# ProPrj_USBuddy_2026-04-30.net
KiCad netlist of a schematic drawn in EasyEDA Pro
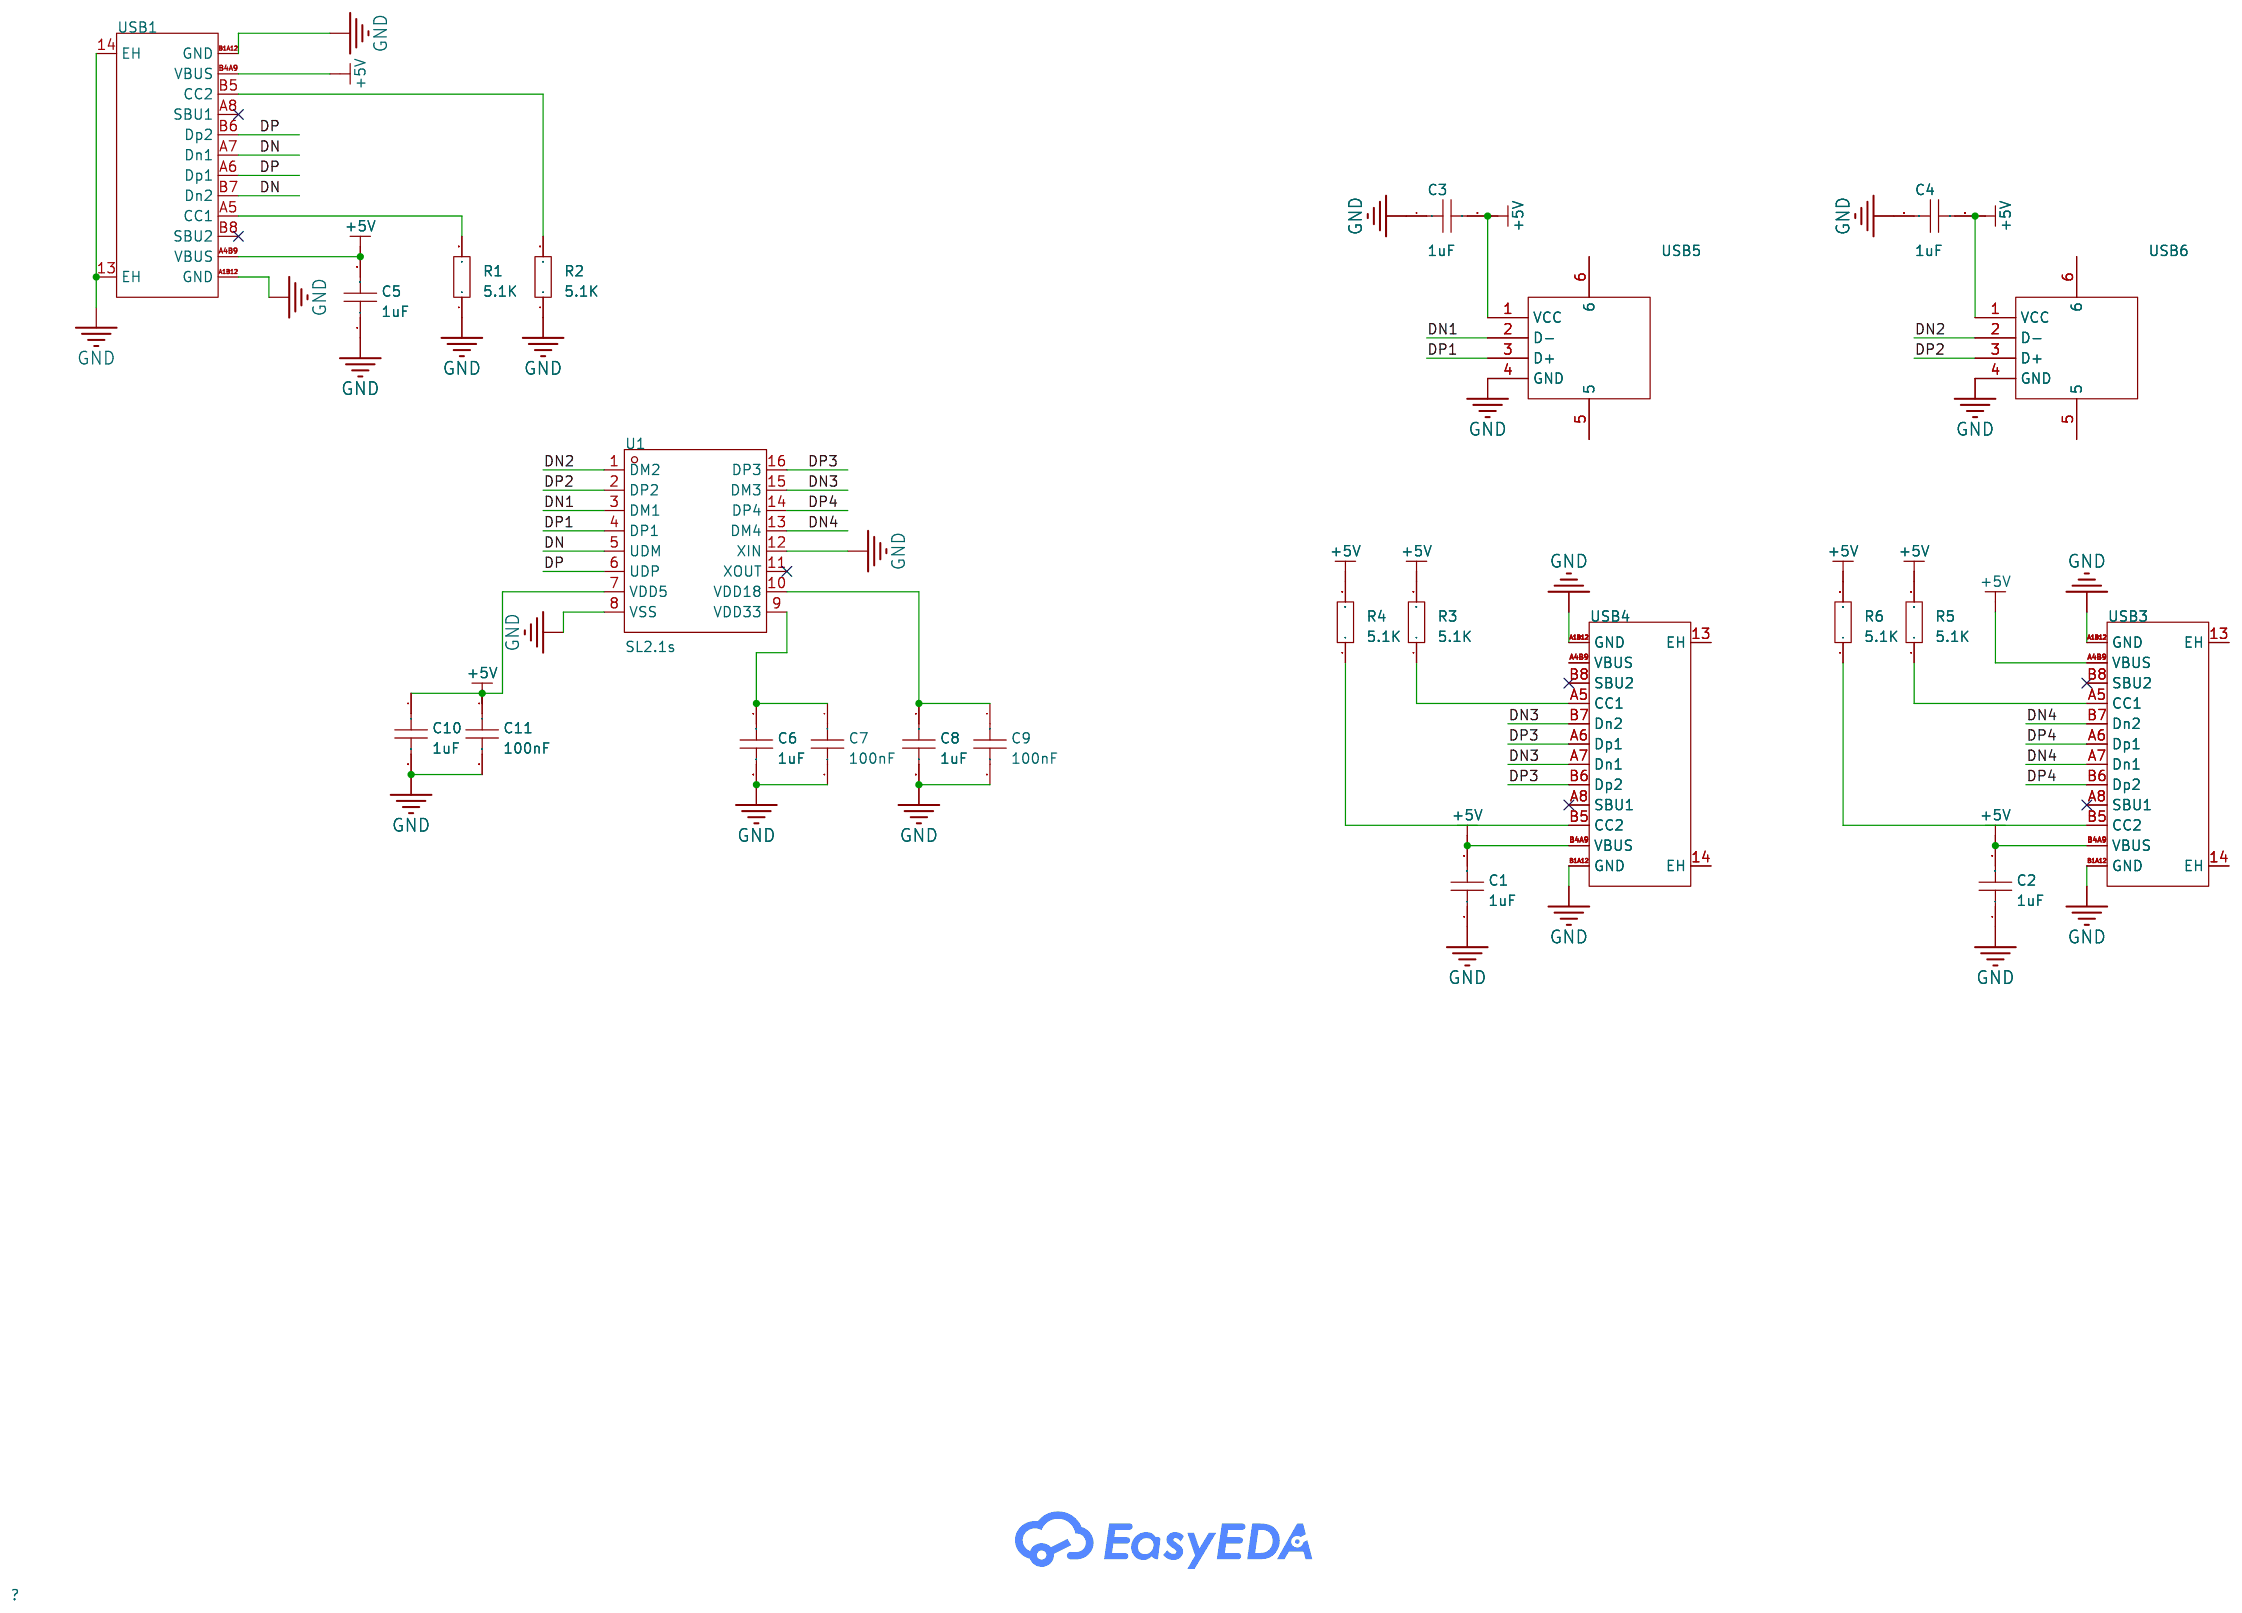
[diagram p0: schematic sheet]

(export (version "E")
  (design (tool "Eeschema 10.0.6"))
  (components
    (comp (ref "C1") (value "1uF") (footprint "easyedapro:C0603") (libsource (lib "easyedapro") (part "CAP")))
    (comp (ref "C2") (value "1uF") (footprint "easyedapro:C0603") (libsource (lib "easyedapro") (part "CAP")))
    (comp (ref "C3") (value "1uF") (footprint "easyedapro:C0603") (libsource (lib "easyedapro") (part "CAP")))
    (comp (ref "C4") (value "1uF") (footprint "easyedapro:C0603") (libsource (lib "easyedapro") (part "CAP")))
    (comp (ref "C5") (value "1uF") (footprint "easyedapro:C0603") (libsource (lib "easyedapro") (part "CAP")))
    (comp (ref "C6") (value "1uF") (footprint "easyedapro:C0603") (libsource (lib "easyedapro") (part "CAP")))
    (comp (ref "C7")
      (value "100nF")
      (footprint "easyedapro:C0603")
      (libsource (lib "easyedapro") (part "CAP"))
    )
    (comp (ref "C8") (value "1uF") (footprint "easyedapro:C0603") (libsource (lib "easyedapro") (part "CAP")))
    (comp (ref "C9")
      (value "100nF")
      (footprint "easyedapro:C0603")
      (libsource (lib "easyedapro") (part "CAP"))
    )
    (comp (ref "C10")
      (value "1uF")
      (footprint "easyedapro:C0603")
      (libsource (lib "easyedapro") (part "CAP"))
    )
    (comp (ref "C11")
      (value "100nF")
      (footprint "easyedapro:C0603")
      (libsource (lib "easyedapro") (part "CAP"))
    )
    (comp (ref "R1")
      (value "5.1K")
      (footprint "easyedapro:R0603")
      (libsource (lib "easyedapro") (part "Res"))
    )
    (comp (ref "R2")
      (value "5.1K")
      (footprint "easyedapro:R0603")
      (libsource (lib "easyedapro") (part "Res"))
    )
    (comp (ref "R3")
      (value "5.1K")
      (footprint "easyedapro:R0603")
      (libsource (lib "easyedapro") (part "Res"))
    )
    (comp (ref "R4")
      (value "5.1K")
      (footprint "easyedapro:R0603")
      (libsource (lib "easyedapro") (part "Res"))
    )
    (comp (ref "R5")
      (value "5.1K")
      (footprint "easyedapro:R0603")
      (libsource (lib "easyedapro") (part "Res"))
    )
    (comp (ref "R6")
      (value "5.1K")
      (footprint "easyedapro:R0603")
      (libsource (lib "easyedapro") (part "Res"))
    )
    (comp (ref "U1")
      (value "SL2.1s")
      (footprint "easyedapro:SSOP-16_L4.6-W2.6-P0.53-LS4.0-BL")
      (fields (field (name "Manufacturer") "CoreChips(和芯润德)"))
      (libsource (lib "easyedapro") (part "SL2.1S"))
    )
    (comp (ref "USB1")
      (value "TYPE-C 16PIN 2MD(073)")
      (footprint "easyedapro:USB-C-SMD_TYPE-C-16PIN-2MD-073")
      (fields (field (name "Manufacturer") "SHOU HAN(首韩)"))
      (libsource (lib "easyedapro") (part "TYPE-C 16PIN 2MD(073)"))
    )
    (comp (ref "USB3")
      (value "TYPE-C 16PIN 2MD(073)")
      (footprint "easyedapro:USB-C-SMD_TYPE-C-16PIN-2MD-073")
      (fields (field (name "Manufacturer") "SHOU HAN(首韩)"))
      (libsource (lib "easyedapro") (part "TYPE-C 16PIN 2MD(073)"))
    )
    (comp (ref "USB4")
      (value "TYPE-C 16PIN 2MD(073)")
      (footprint "easyedapro:USB-C-SMD_TYPE-C-16PIN-2MD-073")
      (fields (field (name "Manufacturer") "SHOU HAN(首韩)"))
      (libsource (lib "easyedapro") (part "TYPE-C 16PIN 2MD(073)"))
    )
    (comp (ref "USB5")
      (value "10.0 QHHTZB6.3")
      (footprint "easyedapro:USB-A-TH_10.0QHHTZB6.3")
      (fields (field (name "Manufacturer") "SHOU HAN(首韩)"))
      (libsource (lib "easyedapro") (part "10.0 QHHTZB6.3"))
    )
    (comp (ref "USB6")
      (value "10.0 QHHTZB6.3")
      (footprint "easyedapro:USB-A-TH_10.0QHHTZB6.3")
      (fields (field (name "Manufacturer") "SHOU HAN(首韩)"))
      (libsource (lib "easyedapro") (part "10.0 QHHTZB6.3"))
    )
  )
  (nets
    (net (code "1") (name "+5V") (class "Default")
      (node (ref "C1") (pin "2") (pinfunction "2_2") (pintype "input"))
      (node (ref "C10") (pin "1") (pinfunction "1_1") (pintype "input"))
      (node (ref "C11") (pin "1") (pinfunction "1_1") (pintype "input"))
      (node (ref "C2") (pin "2") (pinfunction "2_2") (pintype "input"))
      (node (ref "C3") (pin "2") (pinfunction "2_2") (pintype "input"))
      (node (ref "C4") (pin "2") (pinfunction "2_2") (pintype "input"))
      (node (ref "C5") (pin "2") (pinfunction "2_2") (pintype "input"))
      (node (ref "R3") (pin "2") (pinfunction "2_2") (pintype "input"))
      (node (ref "R4") (pin "2") (pinfunction "2_2") (pintype "input"))
      (node (ref "R5") (pin "2") (pinfunction "2_2") (pintype "input"))
      (node (ref "R6") (pin "2") (pinfunction "2_2") (pintype "input"))
      (node (ref "U1") (pin "7") (pinfunction "VDD5_7") (pintype "unspecified"))
      (node (ref "USB1") (pin "A4B9") (pinfunction "VBUS_A4B9") (pintype "unspecified"))
      (node (ref "USB1") (pin "B4A9") (pinfunction "VBUS_B4A9") (pintype "unspecified"))
      (node (ref "USB3") (pin "A4B9") (pinfunction "VBUS_A4B9") (pintype "unspecified"))
      (node (ref "USB3") (pin "B4A9") (pinfunction "VBUS_B4A9") (pintype "unspecified"))
      (node (ref "USB4") (pin "B4A9") (pinfunction "VBUS_B4A9") (pintype "unspecified"))
      (node (ref "USB5") (pin "1") (pinfunction "VCC_1") (pintype "unspecified"))
      (node (ref "USB6") (pin "1") (pinfunction "VCC_1") (pintype "unspecified"))
    )
    (net (code "2") (name "/DN") (class "Default")
      (node (ref "U1") (pin "5") (pinfunction "UDM_5") (pintype "unspecified"))
      (node (ref "USB1") (pin "A7") (pinfunction "Dn1_A7") (pintype "unspecified"))
      (node (ref "USB1") (pin "B7") (pinfunction "Dn2_B7") (pintype "unspecified"))
    )
    (net (code "3") (name "/DN1") (class "Default")
      (node (ref "U1") (pin "3") (pinfunction "DM1_3") (pintype "unspecified"))
      (node (ref "USB5") (pin "2") (pinfunction "D-_2") (pintype "unspecified"))
    )
    (net (code "4") (name "/DN2") (class "Default")
      (node (ref "U1") (pin "1") (pinfunction "DM2_1") (pintype "unspecified"))
      (node (ref "USB6") (pin "2") (pinfunction "D-_2") (pintype "unspecified"))
    )
    (net (code "5") (name "/DN3") (class "Default")
      (node (ref "U1") (pin "15") (pinfunction "DM3_15") (pintype "unspecified"))
      (node (ref "USB4") (pin "A7") (pinfunction "Dn1_A7") (pintype "unspecified"))
      (node (ref "USB4") (pin "B7") (pinfunction "Dn2_B7") (pintype "unspecified"))
    )
    (net (code "6") (name "/DN4") (class "Default")
      (node (ref "U1") (pin "13") (pinfunction "DM4_13") (pintype "unspecified"))
      (node (ref "USB3") (pin "A7") (pinfunction "Dn1_A7") (pintype "unspecified"))
      (node (ref "USB3") (pin "B7") (pinfunction "Dn2_B7") (pintype "unspecified"))
    )
    (net (code "7") (name "/DP") (class "Default")
      (node (ref "U1") (pin "6") (pinfunction "UDP_6") (pintype "unspecified"))
      (node (ref "USB1") (pin "A6") (pinfunction "Dp1_A6") (pintype "unspecified"))
      (node (ref "USB1") (pin "B6") (pinfunction "Dp2_B6") (pintype "unspecified"))
    )
    (net (code "8") (name "/DP1") (class "Default")
      (node (ref "U1") (pin "4") (pinfunction "DP1_4") (pintype "unspecified"))
      (node (ref "USB5") (pin "3") (pinfunction "D+_3") (pintype "unspecified"))
    )
    (net (code "9") (name "/DP2") (class "Default")
      (node (ref "U1") (pin "2") (pinfunction "DP2_2") (pintype "unspecified"))
      (node (ref "USB6") (pin "3") (pinfunction "D+_3") (pintype "unspecified"))
    )
    (net (code "10") (name "/DP3") (class "Default")
      (node (ref "U1") (pin "16") (pinfunction "DP3_16") (pintype "unspecified"))
      (node (ref "USB4") (pin "A6") (pinfunction "Dp1_A6") (pintype "unspecified"))
      (node (ref "USB4") (pin "B6") (pinfunction "Dp2_B6") (pintype "unspecified"))
    )
    (net (code "11") (name "/DP4") (class "Default")
      (node (ref "U1") (pin "14") (pinfunction "DP4_14") (pintype "unspecified"))
      (node (ref "USB3") (pin "A6") (pinfunction "Dp1_A6") (pintype "unspecified"))
      (node (ref "USB3") (pin "B6") (pinfunction "Dp2_B6") (pintype "unspecified"))
    )
    (net (code "12") (name "GND") (class "Default")
      (node (ref "C1") (pin "1") (pinfunction "1_1") (pintype "input"))
      (node (ref "C10") (pin "2") (pinfunction "2_2") (pintype "input"))
      (node (ref "C11") (pin "2") (pinfunction "2_2") (pintype "input"))
      (node (ref "C2") (pin "1") (pinfunction "1_1") (pintype "input"))
      (node (ref "C3") (pin "1") (pinfunction "1_1") (pintype "input"))
      (node (ref "C4") (pin "1") (pinfunction "1_1") (pintype "input"))
      (node (ref "C5") (pin "1") (pinfunction "1_1") (pintype "input"))
      (node (ref "C6") (pin "2") (pinfunction "2_2") (pintype "input"))
      (node (ref "C7") (pin "2") (pinfunction "2_2") (pintype "input"))
      (node (ref "C8") (pin "2") (pinfunction "2_2") (pintype "input"))
      (node (ref "C9") (pin "2") (pinfunction "2_2") (pintype "input"))
      (node (ref "R1") (pin "1") (pinfunction "1_1") (pintype "input"))
      (node (ref "R2") (pin "1") (pinfunction "1_1") (pintype "input"))
      (node (ref "U1") (pin "12") (pinfunction "XIN_12") (pintype "unspecified"))
      (node (ref "U1") (pin "8") (pinfunction "VSS_8") (pintype "unspecified"))
      (node (ref "USB1") (pin "13") (pinfunction "EH_13") (pintype "unspecified"))
      (node (ref "USB1") (pin "14") (pinfunction "EH_14") (pintype "unspecified"))
      (node (ref "USB1") (pin "A1B12") (pinfunction "GND_A1B12") (pintype "unspecified"))
      (node (ref "USB1") (pin "B1A12") (pinfunction "GND_B1A12") (pintype "unspecified"))
      (node (ref "USB3") (pin "A1B12") (pinfunction "GND_A1B12") (pintype "unspecified"))
      (node (ref "USB3") (pin "B1A12") (pinfunction "GND_B1A12") (pintype "unspecified"))
      (node (ref "USB4") (pin "A1B12") (pinfunction "GND_A1B12") (pintype "unspecified"))
      (node (ref "USB4") (pin "B1A12") (pinfunction "GND_B1A12") (pintype "unspecified"))
      (node (ref "USB5") (pin "4") (pinfunction "GND_4") (pintype "unspecified"))
      (node (ref "USB6") (pin "4") (pinfunction "GND_4") (pintype "unspecified"))
    )
    (net (code "13") (name "Net-(U1-VDD18)") (class "Default")
      (node (ref "C8") (pin "1") (pinfunction "1_1") (pintype "input"))
      (node (ref "C9") (pin "1") (pinfunction "1_1") (pintype "input"))
      (node (ref "U1") (pin "10") (pinfunction "VDD18_10") (pintype "unspecified"))
    )
    (net (code "14") (name "Net-(U1-VDD33)") (class "Default")
      (node (ref "C6") (pin "1") (pinfunction "1_1") (pintype "input"))
      (node (ref "C7") (pin "1") (pinfunction "1_1") (pintype "input"))
      (node (ref "U1") (pin "9") (pinfunction "VDD33_9") (pintype "unspecified"))
    )
    (net (code "15") (name "Net-(USB1-CC1)") (class "Default")
      (node (ref "R1") (pin "2") (pinfunction "2_2") (pintype "input"))
      (node (ref "USB1") (pin "A5") (pinfunction "CC1_A5") (pintype "unspecified"))
    )
    (net (code "16") (name "Net-(USB1-CC2)") (class "Default")
      (node (ref "R2") (pin "2") (pinfunction "2_2") (pintype "input"))
      (node (ref "USB1") (pin "B5") (pinfunction "CC2_B5") (pintype "unspecified"))
    )
    (net (code "17") (name "Net-(USB3-CC1)") (class "Default")
      (node (ref "R5") (pin "1") (pinfunction "1_1") (pintype "input"))
      (node (ref "USB3") (pin "A5") (pinfunction "CC1_A5") (pintype "unspecified"))
    )
    (net (code "18") (name "Net-(USB3-CC2)") (class "Default")
      (node (ref "R6") (pin "1") (pinfunction "1_1") (pintype "input"))
      (node (ref "USB3") (pin "B5") (pinfunction "CC2_B5") (pintype "unspecified"))
    )
    (net (code "19") (name "Net-(USB4-CC1)") (class "Default")
      (node (ref "R3") (pin "1") (pinfunction "1_1") (pintype "input"))
      (node (ref "USB4") (pin "A5") (pinfunction "CC1_A5") (pintype "unspecified"))
    )
    (net (code "20") (name "Net-(USB4-CC2)") (class "Default")
      (node (ref "R4") (pin "1") (pinfunction "1_1") (pintype "input"))
      (node (ref "USB4") (pin "B5") (pinfunction "CC2_B5") (pintype "unspecified"))
    )
    (net (code "21") (name "unconnected-(U1-XOUT-Pad11)") (class "Default")
      (node (ref "U1") (pin "11") (pinfunction "XOUT_11") (pintype "unspecified+no_connect"))
    )
    (net (code "22") (name "unconnected-(USB1-SBU1-PadA8)") (class "Default")
      (node (ref "USB1") (pin "A8") (pinfunction "SBU1_A8") (pintype "unspecified+no_connect"))
    )
    (net (code "23") (name "unconnected-(USB1-SBU2-PadB8)") (class "Default")
      (node (ref "USB1") (pin "B8") (pinfunction "SBU2_B8") (pintype "unspecified+no_connect"))
    )
    (net (code "24") (name "unconnected-(USB3-EH-Pad13)") (class "Default")
      (node (ref "USB3") (pin "13") (pinfunction "EH_13") (pintype "unspecified"))
    )
    (net (code "25") (name "unconnected-(USB3-EH-Pad14)") (class "Default")
      (node (ref "USB3") (pin "14") (pinfunction "EH_14") (pintype "unspecified"))
    )
    (net (code "26") (name "unconnected-(USB3-SBU1-PadA8)") (class "Default")
      (node (ref "USB3") (pin "A8") (pinfunction "SBU1_A8") (pintype "unspecified+no_connect"))
    )
    (net (code "27") (name "unconnected-(USB3-SBU2-PadB8)") (class "Default")
      (node (ref "USB3") (pin "B8") (pinfunction "SBU2_B8") (pintype "unspecified+no_connect"))
    )
    (net (code "28") (name "unconnected-(USB4-EH-Pad13)") (class "Default")
      (node (ref "USB4") (pin "13") (pinfunction "EH_13") (pintype "unspecified"))
    )
    (net (code "29") (name "unconnected-(USB4-EH-Pad14)") (class "Default")
      (node (ref "USB4") (pin "14") (pinfunction "EH_14") (pintype "unspecified"))
    )
    (net (code "30") (name "unconnected-(USB4-SBU1-PadA8)") (class "Default")
      (node (ref "USB4") (pin "A8") (pinfunction "SBU1_A8") (pintype "unspecified+no_connect"))
    )
    (net (code "31") (name "unconnected-(USB4-SBU2-PadB8)") (class "Default")
      (node (ref "USB4") (pin "B8") (pinfunction "SBU2_B8") (pintype "unspecified+no_connect"))
    )
    (net (code "32") (name "unconnected-(USB4-VBUS-PadA4B9)") (class "Default")
      (node (ref "USB4") (pin "A4B9") (pinfunction "VBUS_A4B9") (pintype "unspecified"))
    )
    (net (code "33") (name "unconnected-(USB5-Pad5)") (class "Default")
      (node (ref "USB5") (pin "5") (pinfunction "5_5") (pintype "unspecified"))
    )
    (net (code "34") (name "unconnected-(USB5-Pad6)") (class "Default")
      (node (ref "USB5") (pin "6") (pinfunction "6_6") (pintype "unspecified"))
    )
    (net (code "35") (name "unconnected-(USB6-Pad5)") (class "Default")
      (node (ref "USB6") (pin "5") (pinfunction "5_5") (pintype "unspecified"))
    )
    (net (code "36") (name "unconnected-(USB6-Pad6)") (class "Default")
      (node (ref "USB6") (pin "6") (pinfunction "6_6") (pintype "unspecified"))
    )
  )
)
